# HalfBridge.net
KiCad netlist of a schematic drawn in Altium Designer
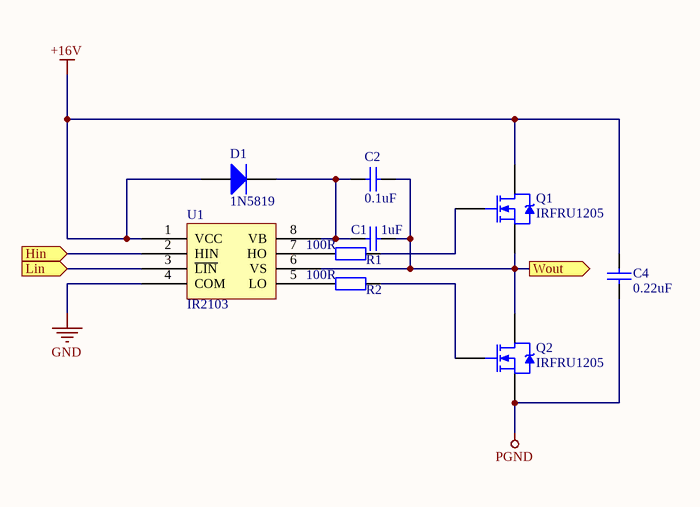
[diagram p0: HalfBridge.SchDoc]

(export (version "E")
  (design (tool "Eeschema 10.0.6"))
  (components
    (comp (ref "C1") (value "1uF") (footprint "0603") (libsource (lib "Integrated_Library2") (part "cap")))
    (comp (ref "C2") (value "0.1uF") (footprint "0603") (libsource (lib "Integrated_Library2") (part "cap")))
    (comp (ref "C4") (value "0.22uF") (footprint "0603") (libsource (lib "Integrated_Library2") (part "cap")))
    (comp (ref "D1")
      (value "1N5819")
      (footprint "SOD-123")
      (libsource (lib "Integrated_Library2") (part "diode"))
    )
    (comp (ref "Q1")
      (value "IRFRU1205")
      (footprint "TO-252")
      (libsource (lib "Integrated_Library2") (part "IRFRU1205"))
    )
    (comp (ref "Q2")
      (value "IRFRU1205")
      (footprint "TO-252")
      (libsource (lib "Integrated_Library2") (part "IRFRU1205"))
    )
    (comp (ref "R1") (value "100R") (footprint "0603") (libsource (lib "Integrated_Library2") (part "res")))
    (comp (ref "R2") (value "100R") (footprint "0603") (libsource (lib "Integrated_Library2") (part "res")))
    (comp (ref "U1")
      (value "IR2103")
      (footprint "SOIC-8")
      (libsource (lib "Integrated_Library2") (part "IR2103"))
    )
  )
  (nets
    (net (code "1") (name "+16V") (class "Default")
      (node (ref "C4") (pin "2") (pinfunction "2_2") (pintype "passive"))
      (node (ref "D1") (pin "A") (pinfunction "A_A") (pintype "passive"))
      (node (ref "Q1") (pin "2") (pinfunction "D_2") (pintype "passive"))
      (node (ref "U1") (pin "1") (pinfunction "VCC_1") (pintype "passive"))
    )
    (net (code "2") (name "/Hin") (class "Default")
      (node (ref "U1") (pin "2") (pinfunction "HIN_2") (pintype "passive"))
    )
    (net (code "3") (name "/Lin") (class "Default")
      (node (ref "U1") (pin "3") (pinfunction "~{LIN}_3") (pintype "passive"))
    )
    (net (code "4") (name "/Wout") (class "Default")
      (node (ref "C1") (pin "2") (pinfunction "2_2") (pintype "passive"))
      (node (ref "C2") (pin "2") (pinfunction "2_2") (pintype "passive"))
      (node (ref "Q1") (pin "3") (pinfunction "S_3") (pintype "passive"))
      (node (ref "Q2") (pin "2") (pinfunction "D_2") (pintype "passive"))
      (node (ref "U1") (pin "6") (pinfunction "VS_6") (pintype "passive"))
    )
    (net (code "5") (name "GND") (class "Default")
      (node (ref "U1") (pin "4") (pinfunction "COM_4") (pintype "passive"))
    )
    (net (code "6") (name "Net-(Q1-G)") (class "Default")
      (node (ref "Q1") (pin "1") (pinfunction "G_1") (pintype "passive"))
      (node (ref "R1") (pin "2") (pinfunction "2_2") (pintype "passive"))
    )
    (net (code "7") (name "Net-(Q2-G)") (class "Default")
      (node (ref "Q2") (pin "1") (pinfunction "G_1") (pintype "passive"))
      (node (ref "R2") (pin "2") (pinfunction "2_2") (pintype "passive"))
    )
    (net (code "8") (name "Net-(U1-HO)") (class "Default")
      (node (ref "R1") (pin "1") (pinfunction "1_1") (pintype "passive"))
      (node (ref "U1") (pin "7") (pinfunction "HO_7") (pintype "passive"))
    )
    (net (code "9") (name "Net-(U1-LO)") (class "Default")
      (node (ref "R2") (pin "1") (pinfunction "1_1") (pintype "passive"))
      (node (ref "U1") (pin "5") (pinfunction "LO_5") (pintype "passive"))
    )
    (net (code "10") (name "Net-(U1-VB)") (class "Default")
      (node (ref "C1") (pin "1") (pinfunction "1_1") (pintype "passive"))
      (node (ref "C2") (pin "1") (pinfunction "1_1") (pintype "passive"))
      (node (ref "D1") (pin "K") (pinfunction "K_K") (pintype "passive"))
      (node (ref "U1") (pin "8") (pinfunction "VB_8") (pintype "passive"))
    )
    (net (code "11") (name "PGND") (class "Default")
      (node (ref "C4") (pin "1") (pinfunction "1_1") (pintype "passive"))
      (node (ref "Q2") (pin "3") (pinfunction "S_3") (pintype "passive"))
    )
  )
)
